# Motion.net
KiCad netlist of a schematic drawn in EAGLE
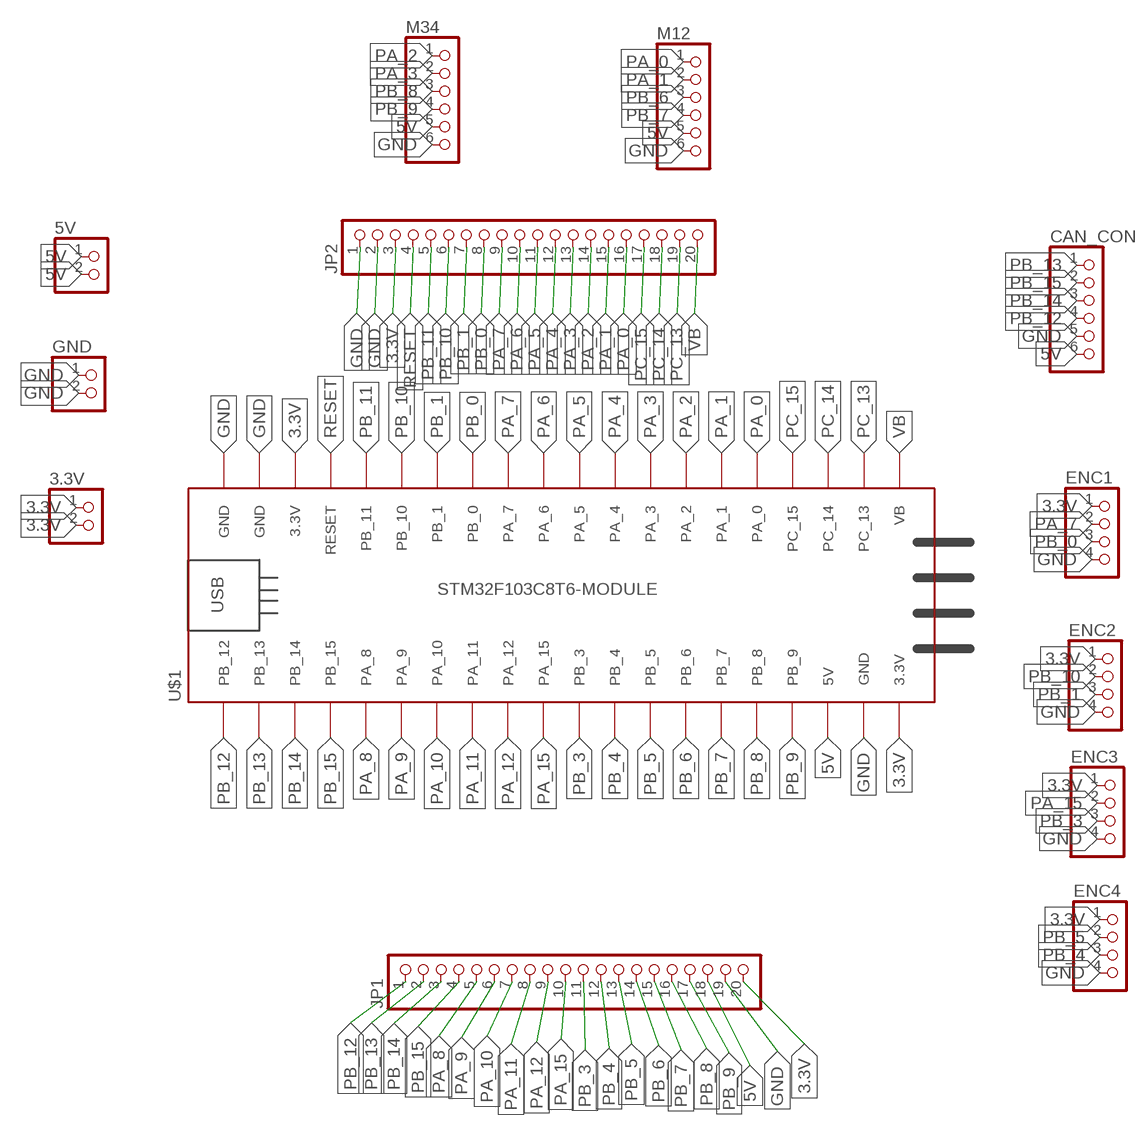
[diagram p0: schematic, sheet 1]

(export (version "E")
  (design (tool "Eeschema 10.0.6"))
  (components
    (comp (ref "3.3V")
      (value "PINHD-2_DATA")
      (footprint "eagle-import:1X02_DATA")
      (libsource (lib "eagle-import") (part "PINHD-2_DATA"))
    )
    (comp (ref "5V")
      (value "PINHD-2_DATA")
      (footprint "eagle-import:1X02_DATA")
      (libsource (lib "eagle-import") (part "PINHD-2_DATA"))
    )
    (comp (ref "CAN_CON")
      (value "PINHD-6_DATA")
      (footprint "eagle-import:1X06_DATA")
      (libsource (lib "eagle-import") (part "PINHD-6_DATA"))
    )
    (comp (ref "ENC1")
      (value "PINHD-4_DATA")
      (footprint "eagle-import:1X04_DATA")
      (libsource (lib "eagle-import") (part "PINHD-4_DATA"))
    )
    (comp (ref "ENC2")
      (value "PINHD-4_DATA")
      (footprint "eagle-import:1X04_DATA")
      (libsource (lib "eagle-import") (part "PINHD-4_DATA"))
    )
    (comp (ref "ENC3")
      (value "PINHD-4_DATA")
      (footprint "eagle-import:1X04_DATA")
      (libsource (lib "eagle-import") (part "PINHD-4_DATA"))
    )
    (comp (ref "ENC4")
      (value "PINHD-4_DATA")
      (footprint "eagle-import:1X04_DATA")
      (libsource (lib "eagle-import") (part "PINHD-4_DATA"))
    )
    (comp (ref "GND")
      (value "PINHD-2_DATA")
      (footprint "eagle-import:1X02_DATA")
      (libsource (lib "eagle-import") (part "PINHD-2_DATA"))
    )
    (comp (ref "JP1")
      (value "PINHD-1X20")
      (footprint "eagle-import:1X20")
      (libsource (lib "eagle-import") (part "PINHD-1X20"))
    )
    (comp (ref "JP2")
      (value "PINHD-1X20")
      (footprint "eagle-import:1X20")
      (libsource (lib "eagle-import") (part "PINHD-1X20"))
    )
    (comp (ref "M12")
      (value "PINHD-1X6")
      (footprint "eagle-import:1X06")
      (libsource (lib "eagle-import") (part "PINHD-1X6"))
    )
    (comp (ref "M34")
      (value "PINHD-1X6")
      (footprint "eagle-import:1X06")
      (libsource (lib "eagle-import") (part "PINHD-1X6"))
    )
    (comp (ref "U$1")
      (value "STM32F103C8T6-MODULE")
      (footprint "eagle-import:STM32F103C8T6-MODULE")
      (libsource (lib "eagle-import") (part "STM32F103C8T6-MODULE"))
    )
  )
  (nets
    (net (code "1") (name "3.3V") (class "Default")
      (node (ref "3.3V") (pin "1") (pinfunction "1_1") (pintype "passive"))
      (node (ref "3.3V") (pin "2") (pinfunction "2_2") (pintype "passive"))
      (node (ref "ENC1") (pin "1") (pinfunction "1_1") (pintype "passive"))
      (node (ref "ENC2") (pin "1") (pinfunction "1_1") (pintype "passive"))
      (node (ref "ENC3") (pin "1") (pinfunction "1_1") (pintype "passive"))
      (node (ref "ENC4") (pin "1") (pinfunction "1_1") (pintype "passive"))
      (node (ref "JP1") (pin "20") (pinfunction "20_20") (pintype "passive"))
      (node (ref "JP2") (pin "3") (pinfunction "3_3") (pintype "passive"))
      (node (ref "U$1") (pin "3.3V_1") (pinfunction "3.3V_3.3V_1") (pintype "bidirectional"))
      (node (ref "U$1") (pin "3.3V_2") (pinfunction "3.3V_3.3V_2") (pintype "bidirectional"))
    )
    (net (code "2") (name "5V") (class "Default")
      (node (ref "5V") (pin "1") (pinfunction "1_1") (pintype "passive"))
      (node (ref "5V") (pin "2") (pinfunction "2_2") (pintype "passive"))
      (node (ref "CAN_CON") (pin "6") (pinfunction "6_6") (pintype "passive"))
      (node (ref "JP1") (pin "18") (pinfunction "18_18") (pintype "passive"))
      (node (ref "M12") (pin "5") (pinfunction "5_5") (pintype "passive"))
      (node (ref "M34") (pin "5") (pinfunction "5_5") (pintype "passive"))
      (node (ref "U$1") (pin "5V") (pinfunction "5V_5V") (pintype "bidirectional"))
    )
    (net (code "3") (name "GND") (class "Default")
      (node (ref "CAN_CON") (pin "5") (pinfunction "5_5") (pintype "passive"))
      (node (ref "ENC1") (pin "4") (pinfunction "4_4") (pintype "passive"))
      (node (ref "ENC2") (pin "4") (pinfunction "4_4") (pintype "passive"))
      (node (ref "ENC3") (pin "4") (pinfunction "4_4") (pintype "passive"))
      (node (ref "ENC4") (pin "4") (pinfunction "4_4") (pintype "passive"))
      (node (ref "GND") (pin "1") (pinfunction "1_1") (pintype "passive"))
      (node (ref "GND") (pin "2") (pinfunction "2_2") (pintype "passive"))
      (node (ref "JP1") (pin "19") (pinfunction "19_19") (pintype "passive"))
      (node (ref "JP2") (pin "1") (pinfunction "1_1") (pintype "passive"))
      (node (ref "JP2") (pin "2") (pinfunction "2_2") (pintype "passive"))
      (node (ref "M12") (pin "6") (pinfunction "6_6") (pintype "passive"))
      (node (ref "M34") (pin "6") (pinfunction "6_6") (pintype "passive"))
      (node (ref "U$1") (pin "GND_1") (pinfunction "GND_GND_1") (pintype "bidirectional"))
      (node (ref "U$1") (pin "GND_2") (pinfunction "GND_GND_2") (pintype "bidirectional"))
      (node (ref "U$1") (pin "GND_3") (pinfunction "GND_GND_3") (pintype "power_in"))
    )
    (net (code "4") (name "PA_0") (class "Default")
      (node (ref "JP2") (pin "16") (pinfunction "16_16") (pintype "passive"))
      (node (ref "M12") (pin "1") (pinfunction "1_1") (pintype "passive"))
      (node (ref "U$1") (pin "PA_0") (pinfunction "PA_0_PA_0") (pintype "bidirectional"))
    )
    (net (code "5") (name "PA_1") (class "Default")
      (node (ref "JP2") (pin "15") (pinfunction "15_15") (pintype "passive"))
      (node (ref "M12") (pin "2") (pinfunction "2_2") (pintype "passive"))
      (node (ref "U$1") (pin "PA_1") (pinfunction "PA_1_PA_1") (pintype "bidirectional"))
    )
    (net (code "6") (name "PA_2") (class "Default")
      (node (ref "JP2") (pin "14") (pinfunction "14_14") (pintype "passive"))
      (node (ref "M34") (pin "1") (pinfunction "1_1") (pintype "passive"))
      (node (ref "U$1") (pin "PA_2") (pinfunction "PA_2_PA_2") (pintype "bidirectional"))
    )
    (net (code "7") (name "PA_3") (class "Default")
      (node (ref "JP2") (pin "13") (pinfunction "13_13") (pintype "passive"))
      (node (ref "M34") (pin "2") (pinfunction "2_2") (pintype "passive"))
      (node (ref "U$1") (pin "PA_3") (pinfunction "PA_3_PA_3") (pintype "bidirectional"))
    )
    (net (code "8") (name "PA_4") (class "Default")
      (node (ref "JP2") (pin "12") (pinfunction "12_12") (pintype "passive"))
      (node (ref "U$1") (pin "PA_4") (pinfunction "PA_4_PA_4") (pintype "bidirectional"))
    )
    (net (code "9") (name "PA_5") (class "Default")
      (node (ref "JP2") (pin "11") (pinfunction "11_11") (pintype "passive"))
      (node (ref "U$1") (pin "PA_5") (pinfunction "PA_5_PA_5") (pintype "bidirectional"))
    )
    (net (code "10") (name "PA_6") (class "Default")
      (node (ref "JP2") (pin "10") (pinfunction "10_10") (pintype "passive"))
      (node (ref "U$1") (pin "PA_6") (pinfunction "PA_6_PA_6") (pintype "bidirectional"))
    )
    (net (code "11") (name "PA_7") (class "Default")
      (node (ref "ENC1") (pin "2") (pinfunction "2_2") (pintype "passive"))
      (node (ref "JP2") (pin "9") (pinfunction "9_9") (pintype "passive"))
      (node (ref "U$1") (pin "PA_7") (pinfunction "PA_7_PA_7") (pintype "bidirectional"))
    )
    (net (code "12") (name "PA_8") (class "Default")
      (node (ref "JP1") (pin "5") (pinfunction "5_5") (pintype "passive"))
      (node (ref "U$1") (pin "PA_8") (pinfunction "PA_8_PA_8") (pintype "bidirectional"))
    )
    (net (code "13") (name "PA_9") (class "Default")
      (node (ref "JP1") (pin "6") (pinfunction "6_6") (pintype "passive"))
      (node (ref "U$1") (pin "PA_9") (pinfunction "PA_9_PA_9") (pintype "bidirectional"))
    )
    (net (code "14") (name "PA_10") (class "Default")
      (node (ref "JP1") (pin "7") (pinfunction "7_7") (pintype "passive"))
      (node (ref "U$1") (pin "PA_10") (pinfunction "PA_10_PA_10") (pintype "bidirectional"))
    )
    (net (code "15") (name "PA_11") (class "Default")
      (node (ref "JP1") (pin "8") (pinfunction "8_8") (pintype "passive"))
      (node (ref "U$1") (pin "PA_11") (pinfunction "PA_11_PA_11") (pintype "bidirectional"))
    )
    (net (code "16") (name "PA_12") (class "Default")
      (node (ref "JP1") (pin "9") (pinfunction "9_9") (pintype "passive"))
      (node (ref "U$1") (pin "PA_12") (pinfunction "PA_12_PA_12") (pintype "bidirectional"))
    )
    (net (code "17") (name "PA_15") (class "Default")
      (node (ref "ENC3") (pin "2") (pinfunction "2_2") (pintype "passive"))
      (node (ref "JP1") (pin "10") (pinfunction "10_10") (pintype "passive"))
      (node (ref "U$1") (pin "PA_15") (pinfunction "PA_15_PA_15") (pintype "bidirectional"))
    )
    (net (code "18") (name "PB_0") (class "Default")
      (node (ref "ENC1") (pin "3") (pinfunction "3_3") (pintype "passive"))
      (node (ref "JP2") (pin "8") (pinfunction "8_8") (pintype "passive"))
      (node (ref "U$1") (pin "PB_0") (pinfunction "PB_0_PB_0") (pintype "bidirectional"))
    )
    (net (code "19") (name "PB_1") (class "Default")
      (node (ref "ENC2") (pin "3") (pinfunction "3_3") (pintype "passive"))
      (node (ref "JP2") (pin "7") (pinfunction "7_7") (pintype "passive"))
      (node (ref "U$1") (pin "PB_1") (pinfunction "PB_1_PB_1") (pintype "bidirectional"))
    )
    (net (code "20") (name "PB_3") (class "Default")
      (node (ref "ENC3") (pin "3") (pinfunction "3_3") (pintype "passive"))
      (node (ref "JP1") (pin "11") (pinfunction "11_11") (pintype "passive"))
      (node (ref "U$1") (pin "PB_3") (pinfunction "PB_3_PB_3") (pintype "bidirectional"))
    )
    (net (code "21") (name "PB_4") (class "Default")
      (node (ref "ENC4") (pin "3") (pinfunction "3_3") (pintype "passive"))
      (node (ref "JP1") (pin "12") (pinfunction "12_12") (pintype "passive"))
      (node (ref "U$1") (pin "PB_4") (pinfunction "PB_4_PB_4") (pintype "bidirectional"))
    )
    (net (code "22") (name "PB_5") (class "Default")
      (node (ref "ENC4") (pin "2") (pinfunction "2_2") (pintype "passive"))
      (node (ref "JP1") (pin "13") (pinfunction "13_13") (pintype "passive"))
      (node (ref "U$1") (pin "PB_5") (pinfunction "PB_5_PB_5") (pintype "bidirectional"))
    )
    (net (code "23") (name "PB_6") (class "Default")
      (node (ref "JP1") (pin "14") (pinfunction "14_14") (pintype "passive"))
      (node (ref "M12") (pin "3") (pinfunction "3_3") (pintype "passive"))
      (node (ref "U$1") (pin "PB_6") (pinfunction "PB_6_PB_6") (pintype "bidirectional"))
    )
    (net (code "24") (name "PB_7") (class "Default")
      (node (ref "JP1") (pin "15") (pinfunction "15_15") (pintype "passive"))
      (node (ref "M12") (pin "4") (pinfunction "4_4") (pintype "passive"))
      (node (ref "U$1") (pin "PB_7") (pinfunction "PB_7_PB_7") (pintype "bidirectional"))
    )
    (net (code "25") (name "PB_8") (class "Default")
      (node (ref "JP1") (pin "16") (pinfunction "16_16") (pintype "passive"))
      (node (ref "M34") (pin "3") (pinfunction "3_3") (pintype "passive"))
      (node (ref "U$1") (pin "PB_8") (pinfunction "PB_8_PB_8") (pintype "bidirectional"))
    )
    (net (code "26") (name "PB_9") (class "Default")
      (node (ref "JP1") (pin "17") (pinfunction "17_17") (pintype "passive"))
      (node (ref "M34") (pin "4") (pinfunction "4_4") (pintype "passive"))
      (node (ref "U$1") (pin "PB_9") (pinfunction "PB_9_PB_9") (pintype "bidirectional"))
    )
    (net (code "27") (name "PB_10") (class "Default")
      (node (ref "ENC2") (pin "2") (pinfunction "2_2") (pintype "passive"))
      (node (ref "JP2") (pin "6") (pinfunction "6_6") (pintype "passive"))
      (node (ref "U$1") (pin "PB_10") (pinfunction "PB_10_PB_10") (pintype "bidirectional"))
    )
    (net (code "28") (name "PB_11") (class "Default")
      (node (ref "JP2") (pin "5") (pinfunction "5_5") (pintype "passive"))
      (node (ref "U$1") (pin "PB_11") (pinfunction "PB_11_PB_11") (pintype "bidirectional"))
    )
    (net (code "29") (name "PB_12") (class "Default")
      (node (ref "CAN_CON") (pin "4") (pinfunction "4_4") (pintype "passive"))
      (node (ref "JP1") (pin "1") (pinfunction "1_1") (pintype "passive"))
      (node (ref "U$1") (pin "PB_12") (pinfunction "PB_12_PB_12") (pintype "bidirectional"))
    )
    (net (code "30") (name "PB_13") (class "Default")
      (node (ref "CAN_CON") (pin "1") (pinfunction "1_1") (pintype "passive"))
      (node (ref "JP1") (pin "2") (pinfunction "2_2") (pintype "passive"))
      (node (ref "U$1") (pin "PB_13") (pinfunction "PB_13_PB_13") (pintype "bidirectional"))
    )
    (net (code "31") (name "PB_14") (class "Default")
      (node (ref "CAN_CON") (pin "3") (pinfunction "3_3") (pintype "passive"))
      (node (ref "JP1") (pin "3") (pinfunction "3_3") (pintype "passive"))
      (node (ref "U$1") (pin "PB_14") (pinfunction "PB_14_PB_14") (pintype "bidirectional"))
    )
    (net (code "32") (name "PB_15") (class "Default")
      (node (ref "CAN_CON") (pin "2") (pinfunction "2_2") (pintype "passive"))
      (node (ref "JP1") (pin "4") (pinfunction "4_4") (pintype "passive"))
      (node (ref "U$1") (pin "PB_15") (pinfunction "PB_15_PB_15") (pintype "bidirectional"))
    )
    (net (code "33") (name "PC_13") (class "Default")
      (node (ref "JP2") (pin "19") (pinfunction "19_19") (pintype "passive"))
      (node (ref "U$1") (pin "PC_13") (pinfunction "PC_13_PC_13") (pintype "bidirectional"))
    )
    (net (code "34") (name "PC_14") (class "Default")
      (node (ref "JP2") (pin "18") (pinfunction "18_18") (pintype "passive"))
      (node (ref "U$1") (pin "PC_14") (pinfunction "PC_14_PC_14") (pintype "bidirectional"))
    )
    (net (code "35") (name "PC_15") (class "Default")
      (node (ref "JP2") (pin "17") (pinfunction "17_17") (pintype "passive"))
      (node (ref "U$1") (pin "PC_15") (pinfunction "PC_15_PC_15") (pintype "bidirectional"))
    )
    (net (code "36") (name "RESET") (class "Default")
      (node (ref "JP2") (pin "4") (pinfunction "4_4") (pintype "passive"))
      (node (ref "U$1") (pin "RESET") (pinfunction "RESET_RESET") (pintype "bidirectional"))
    )
    (net (code "37") (name "VB") (class "Default")
      (node (ref "JP2") (pin "20") (pinfunction "20_20") (pintype "passive"))
      (node (ref "U$1") (pin "VB") (pinfunction "VB_VB") (pintype "bidirectional"))
    )
  )
)
